# 3_DAC_Control_CH1_V2_0-2_4.net
KiCad netlist of a schematic drawn in Altium Designer
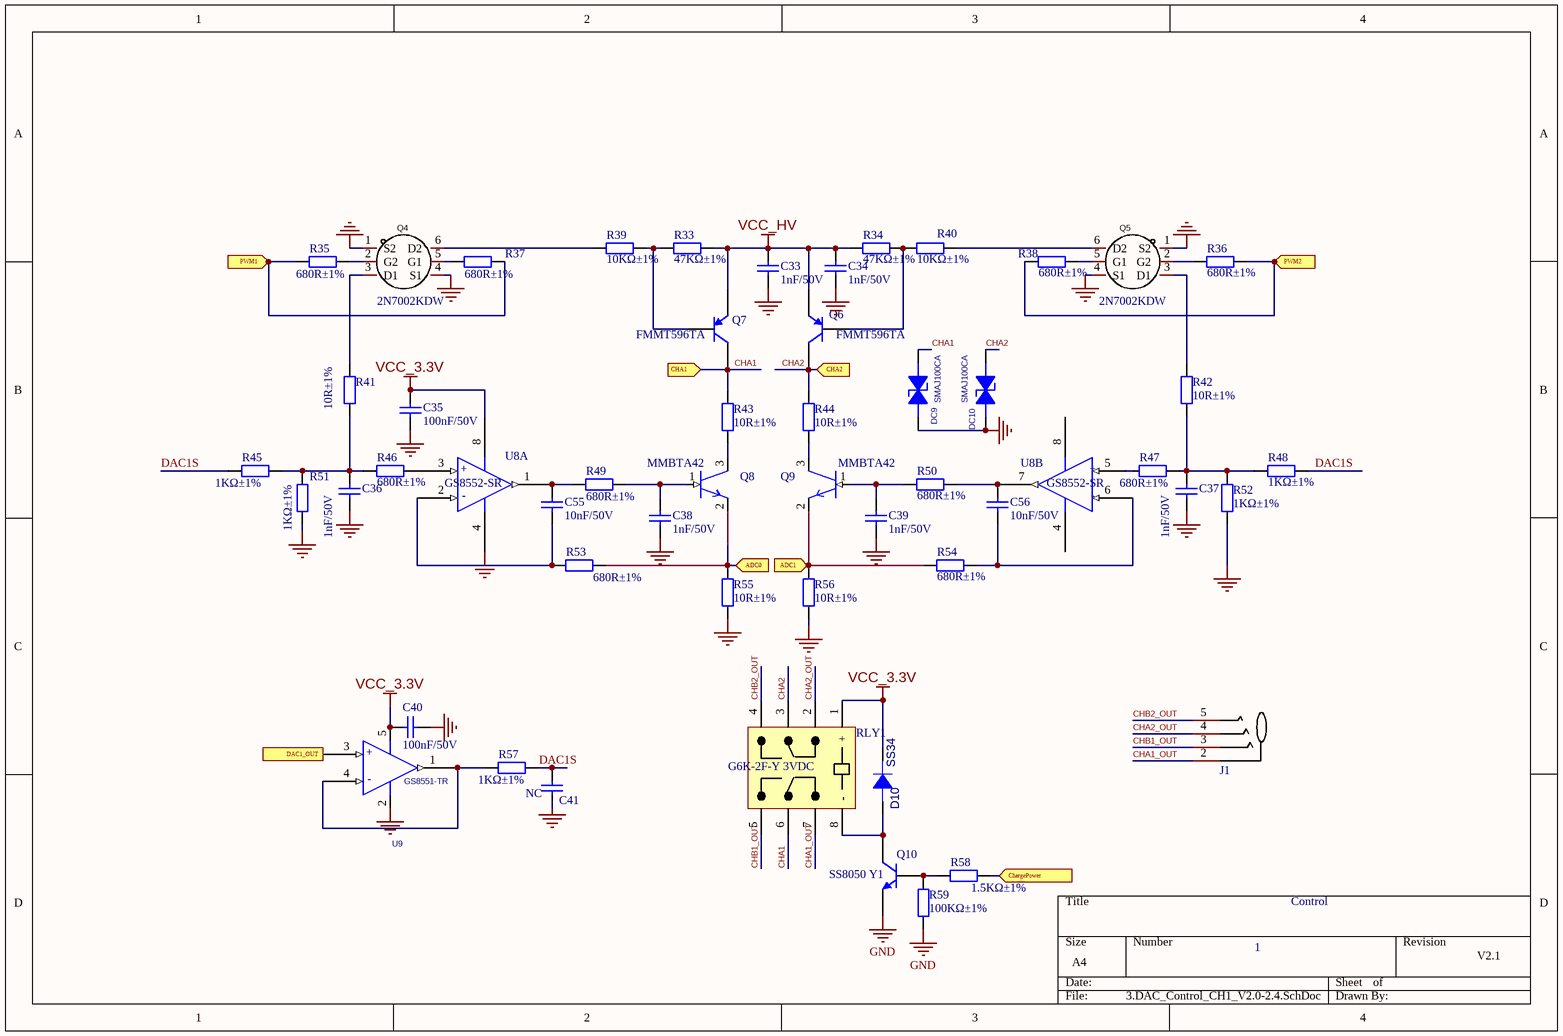
[diagram p0: 3.DAC_Control_CH1_V2.0-2.4.SchDoc]

(export (version "E")
  (design (tool "Eeschema 10.0.6"))
  (components
    (comp (ref "C33")
      (value "1nF/50V")
      (footprint "0603C")
      (description "贴片电容")
      (libsource (lib "Miscellaneous Devices LC") (part "0402 1nF (102) 10% 50V"))
    )
    (comp (ref "C34")
      (value "1nF/50V")
      (footprint "0603C")
      (description "贴片电容")
      (libsource (lib "Miscellaneous Devices LC") (part "0402 1nF (102) 10% 50V"))
    )
    (comp (ref "C35")
      (value "100nF/50V")
      (footprint "0603C")
      (description "贴片电容100nF 10% 50V")
      (libsource (lib "Miscellaneous Devices LC") (part "0402 100nF (104) 10% 16V"))
    )
    (comp (ref "C36")
      (value "1nF/50V")
      (footprint "0603C")
      (description "贴片电容")
      (libsource (lib "Miscellaneous Devices LC") (part "0402 10nF (103) 10% 50V"))
    )
    (comp (ref "C37")
      (value "1nF/50V")
      (footprint "0603C")
      (description "贴片电容")
      (libsource (lib "Miscellaneous Devices LC") (part "0402 10nF (103) 10% 50V"))
    )
    (comp (ref "C38")
      (value "1nF/50V")
      (footprint "0603C")
      (description "贴片电容")
      (libsource (lib "Miscellaneous Devices LC") (part "0402 10nF (103) 10% 50V"))
    )
    (comp (ref "C39")
      (value "1nF/50V")
      (footprint "0603C")
      (description "贴片电容")
      (libsource (lib "Miscellaneous Devices LC") (part "0402 10nF (103) 10% 50V"))
    )
    (comp (ref "C40")
      (value "100nF/50V")
      (footprint "0603C")
      (description "贴片电容100nF 10% 50V")
      (libsource (lib "Miscellaneous Devices LC") (part "0402 100nF (104) 10% 16V"))
    )
    (comp (ref "C41")
      (value "NC")
      (footprint "0603C")
      (description "贴片电容10uF/10V")
      (libsource (lib "Miscellaneous Devices LC") (part "0603 10uF (106) 10% 10V"))
    )
    (comp (ref "C55")
      (value "10nF/50V")
      (footprint "0603C")
      (description "贴片电容")
      (libsource (lib "Miscellaneous Devices LC") (part "0402 10nF (103) 10% 50V"))
    )
    (comp (ref "C56")
      (value "10nF/50V")
      (footprint "0603C")
      (description "贴片电容")
      (libsource (lib "Miscellaneous Devices LC") (part "0402 10nF (103) 10% 50V"))
    )
    (comp (ref "D10")
      (value "SS34")
      (footprint "SMA")
      (description "Schottky Barrier， DO214AA")
      (fields (field (name "MANUFACTURER") "星海") (field (name "CREATED_BY") "JJJ"))
      (libsource (lib "*") (part "DIODE_2"))
    )
    (comp (ref "DC9")
      (value "SMAJ100CA")
      (footprint "SMA")
      (description "SMAJ100CA  SMA(DO-214AC)")
      (libsource (lib "*") (part "ESD5451X_Dup1"))
    )
    (comp (ref "DC10")
      (value "SMAJ100CA")
      (footprint "SMA")
      (description "SMAJ100CA  SMA(DO-214AC)")
      (libsource (lib "*") (part "ESD5451X_Dup1"))
    )
    (comp (ref "J1")
      (value "PJ-320D 贴片4脚")
      (footprint "AUDIO-TH_L14.1-W6.1_PJ-320D")
      (libsource (lib "altium-import") (part "root_2_PJ-320D 贴片4脚_"))
    )
    (comp (ref "Q4")
      (value "2N7002KDW")
      (footprint "SOT-363")
      (description "TECH PUBLIC(台舟) SOT-363")
      (fields (field (name "MANUFACTURER") "TECH PUBLIC(台舟)"))
      (libsource (lib "altium-import") (part "root_0_2N7002KDW_"))
    )
    (comp (ref "Q5")
      (value "2N7002KDW")
      (footprint "SOT-363")
      (description "TECH PUBLIC(台舟) SOT-363")
      (fields (field (name "MANUFACTURER") "TECH PUBLIC(台舟)"))
      (libsource (lib "altium-import") (part "root_0_mirrored_2N7002KDW_"))
    )
    (comp (ref "Q6")
      (value "FMMT596TA")
      (footprint "SOT-23(SOT-23-3)")
      (description "三极管")
      (libsource (lib "Miscellaneous Devices LC") (part "SOT-23 SS8550 Y2"))
    )
    (comp (ref "Q7")
      (value "FMMT596TA")
      (footprint "SOT-23(SOT-23-3)")
      (description "三极管")
      (libsource (lib "Miscellaneous Devices LC") (part "SOT-23 SS8550 Y2"))
    )
    (comp (ref "Q8")
      (value "MMBTA42")
      (footprint "SOT-23")
      (description "CJ(江苏长电/长晶)")
      (libsource (lib "*") (part "NPN"))
    )
    (comp (ref "Q9")
      (value "MMBTA42")
      (footprint "SOT-23")
      (description "CJ(江苏长电/长晶)")
      (libsource (lib "*") (part "NPN"))
    )
    (comp (ref "Q10")
      (value "SS8050 Y1")
      (footprint "SOT-23(SOT-23-3)")
      (description "三极管")
      (libsource (lib "Miscellaneous Devices LC") (part "SOT-23 SS8050 Y1"))
    )
    (comp (ref "R33")
      (value "47KΩ±1%")
      (footprint "0603R")
      (description "贴片电阻")
      (libsource (lib "Miscellaneous Devices LC") (part "0402 1KΩ (1001) 1%"))
    )
    (comp (ref "R34")
      (value "47KΩ±1%")
      (footprint "0603R")
      (description "贴片电阻")
      (libsource (lib "") (part "0402 1KΩ (1001) 1%_1"))
    )
    (comp (ref "R35")
      (value "680R±1%")
      (footprint "0603R")
      (description "贴片电阻")
      (libsource (lib "Miscellaneous Devices LC") (part "0402 680Ω (6800) 1%"))
    )
    (comp (ref "R36")
      (value "680R±1%")
      (footprint "0603R")
      (description "贴片电阻")
      (libsource (lib "") (part "0402 680Ω (6800) 1%_1"))
    )
    (comp (ref "R37")
      (value "680R±1%")
      (footprint "0603R")
      (description "贴片电阻")
      (libsource (lib "Miscellaneous Devices LC") (part "0402 680Ω (6800) 1%"))
    )
    (comp (ref "R38")
      (value "680R±1%")
      (footprint "0603R")
      (description "贴片电阻")
      (libsource (lib "") (part "0402 680Ω (6800) 1%_1"))
    )
    (comp (ref "R39")
      (value "10KΩ±1%")
      (footprint "0603R")
      (description "贴片电阻")
      (libsource (lib "Miscellaneous Devices LC") (part "0402 1KΩ (1001) 1%"))
    )
    (comp (ref "R40")
      (value "10KΩ±1%")
      (footprint "0603R")
      (description "贴片电阻")
      (libsource (lib "") (part "0402 1KΩ (1001) 1%_1"))
    )
    (comp (ref "R41")
      (value "10R±1%")
      (footprint "0603R")
      (description "贴片电阻")
      (libsource (lib "") (part "0603 100Ω (1000) 1%_1"))
    )
    (comp (ref "R42")
      (value "10R±1%")
      (footprint "0603R")
      (description "贴片电阻")
      (libsource (lib "Miscellaneous Devices LC") (part "0603 100Ω (1000) 1%"))
    )
    (comp (ref "R43")
      (value "10R±1%")
      (footprint "0805_R")
      (description "贴片电阻")
      (libsource (lib "") (part "0603 100Ω (1000) 1%_1"))
    )
    (comp (ref "R44")
      (value "10R±1%")
      (footprint "0805_R")
      (description "贴片电阻")
      (libsource (lib "Miscellaneous Devices LC") (part "0603 100Ω (1000) 1%"))
    )
    (comp (ref "R45")
      (value "1KΩ±1%")
      (footprint "0603R")
      (description "贴片电阻")
      (libsource (lib "") (part "0402 1KΩ (1001) 1%_3"))
    )
    (comp (ref "R46")
      (value "680R±1%")
      (footprint "0603R")
      (description "贴片电阻")
      (libsource (lib "Miscellaneous Devices LC") (part "0402 680Ω (6800) 1%"))
    )
    (comp (ref "R47")
      (value "680R±1%")
      (footprint "0603R")
      (description "贴片电阻")
      (libsource (lib "") (part "0402 680Ω (6800) 1%_1"))
    )
    (comp (ref "R48")
      (value "1KΩ±1%")
      (footprint "0603R")
      (description "贴片电阻")
      (libsource (lib "") (part "0402 1KΩ (1001) 1%_2"))
    )
    (comp (ref "R49")
      (value "680R±1%")
      (footprint "0603R")
      (description "贴片电阻")
      (libsource (lib "Miscellaneous Devices LC") (part "0402 680Ω (6800) 1%"))
    )
    (comp (ref "R50")
      (value "680R±1%")
      (footprint "0603R")
      (description "贴片电阻")
      (libsource (lib "") (part "0402 680Ω (6800) 1%_1"))
    )
    (comp (ref "R51")
      (value "1KΩ±1%")
      (footprint "0603R")
      (description "贴片电阻")
      (libsource (lib "") (part "0402 1KΩ (1001) 1%_1"))
    )
    (comp (ref "R52")
      (value "1KΩ±1%")
      (footprint "0603R")
      (description "贴片电阻")
      (libsource (lib "") (part "0402 1KΩ (1001) 1%_3"))
    )
    (comp (ref "R53")
      (value "680R±1%")
      (footprint "0603R")
      (description "贴片电阻")
      (libsource (lib "Miscellaneous Devices LC") (part "0402 680Ω (6800) 1%"))
    )
    (comp (ref "R54")
      (value "680R±1%")
      (footprint "0603R")
      (description "贴片电阻")
      (libsource (lib "") (part "0402 680Ω (6800) 1%_1"))
    )
    (comp (ref "R55")
      (value "10R±1%")
      (footprint "0805_R")
      (description "贴片电阻")
      (libsource (lib "") (part "0603 100Ω (1000) 1%_1"))
    )
    (comp (ref "R56")
      (value "10R±1%")
      (footprint "0805_R")
      (description "贴片电阻")
      (libsource (lib "Miscellaneous Devices LC") (part "0603 100Ω (1000) 1%"))
    )
    (comp (ref "R57")
      (value "1KΩ±1%")
      (footprint "0603R")
      (description "贴片电阻")
      (libsource (lib "Miscellaneous Devices LC") (part "0402 1KΩ (1001) 1%"))
    )
    (comp (ref "R58")
      (value "1.5KΩ±1%")
      (footprint "0402_R")
      (description "贴片电阻")
      (libsource (lib "") (part "0402 1.5KΩ (1501) 1%_1"))
    )
    (comp (ref "R59")
      (value "100KΩ±1%")
      (footprint "0402_R")
      (description "贴片电阻")
      (libsource (lib "Miscellaneous Devices LC") (part "0402 1.5KΩ (1501) 1%"))
    )
    (comp (ref "RLY1")
      (value "G6K-2F-Y 3VDC")
      (footprint "HFD4/12")
      (libsource (lib "MySchLib") (part "RELAY(HF)"))
    )
    (comp (ref "U8")
      (value "GS8552-SR")
      (footprint "SOP-8_150mil")
      (libsource (lib "DESIGN6(1)_Library") (part "GS8552-SR"))
    )
    (comp (ref "U9")
      (value "GS8551-TR")
      (footprint "SOT-23-5")
      (description "GS8551-TR  GS8551 SOT-23-5")
      (fields
        (field (name "MANUFACTURER_PART_NUMBER") "OPA335AIDBVR")
        (field (name "COPYRIGHT") "Copyright (C) 2022 Ultra Librarian. All rights reserved.")
      )
      (libsource (lib "FES_VNS_V1.0x2") (part "OPA335AIDBVR_1"))
    )
  )
  (nets
    (net (code "1") (name "/ADC0") (class "Default")
      (node (ref "Q8") (pin "2") (pinfunction "2_2") (pintype "passive"))
      (node (ref "R53") (pin "2") (pinfunction "2_2") (pintype "passive"))
      (node (ref "R55") (pin "2") (pinfunction "2_2") (pintype "passive"))
    )
    (net (code "2") (name "/ADC1") (class "Default")
      (node (ref "Q9") (pin "2") (pinfunction "2_2") (pintype "passive"))
      (node (ref "R54") (pin "2") (pinfunction "2_2") (pintype "passive"))
      (node (ref "R56") (pin "2") (pinfunction "2_2") (pintype "passive"))
    )
    (net (code "3") (name "/CHA1") (class "Default")
      (node (ref "DC9") (pin "1") (pinfunction "ANODE_1") (pintype "passive"))
      (node (ref "Q7") (pin "3") (pinfunction "C_3") (pintype "passive"))
      (node (ref "R43") (pin "2") (pinfunction "2_2") (pintype "passive"))
      (node (ref "RLY1") (pin "6") (pinfunction "6_6") (pintype "passive"))
    )
    (net (code "4") (name "/CHA1_OUT") (class "Default")
      (node (ref "J1") (pin "2") (pinfunction "2_2") (pintype "passive"))
      (node (ref "RLY1") (pin "7") (pinfunction "7_7") (pintype "passive"))
    )
    (net (code "5") (name "/CHA2") (class "Default")
      (node (ref "DC10") (pin "1") (pinfunction "ANODE_1") (pintype "passive"))
      (node (ref "Q6") (pin "3") (pinfunction "C_3") (pintype "passive"))
      (node (ref "R44") (pin "2") (pinfunction "2_2") (pintype "passive"))
      (node (ref "RLY1") (pin "3") (pinfunction "3_3") (pintype "passive"))
    )
    (net (code "6") (name "/CHA2_OUT") (class "Default")
      (node (ref "J1") (pin "4") (pinfunction "4_4") (pintype "passive"))
      (node (ref "RLY1") (pin "2") (pinfunction "2_2") (pintype "passive"))
    )
    (net (code "7") (name "/CHB1_OUT") (class "Default")
      (node (ref "J1") (pin "3") (pinfunction "3_3") (pintype "passive"))
      (node (ref "RLY1") (pin "5") (pinfunction "5_5") (pintype "passive"))
    )
    (net (code "8") (name "/CHB2_OUT") (class "Default")
      (node (ref "J1") (pin "5") (pinfunction "5_5") (pintype "passive"))
      (node (ref "RLY1") (pin "4") (pinfunction "4_4") (pintype "passive"))
    )
    (net (code "9") (name "/ChargePower") (class "Default")
      (node (ref "R58") (pin "1") (pinfunction "1_1") (pintype "passive"))
    )
    (net (code "10") (name "/DAC1S") (class "Default")
      (node (ref "C41") (pin "2") (pinfunction "2_2") (pintype "passive"))
      (node (ref "R45") (pin "1") (pinfunction "1_1") (pintype "passive"))
      (node (ref "R48") (pin "1") (pinfunction "1_1") (pintype "passive"))
      (node (ref "R57") (pin "1") (pinfunction "1_1") (pintype "passive"))
    )
    (net (code "11") (name "/DAC1_OUT") (class "Default")
      (node (ref "U9") (pin "3") (pinfunction "IN+_3") (pintype "input"))
    )
    (net (code "12") (name "/PWM1") (class "Default")
      (node (ref "R35") (pin "1") (pinfunction "1_1") (pintype "passive"))
      (node (ref "R37") (pin "2") (pinfunction "2_2") (pintype "passive"))
    )
    (net (code "13") (name "/PWM2") (class "Default")
      (node (ref "R36") (pin "1") (pinfunction "1_1") (pintype "passive"))
      (node (ref "R38") (pin "2") (pinfunction "2_2") (pintype "passive"))
    )
    (net (code "14") (name "GND") (class "Default")
      (node (ref "C33") (pin "1") (pinfunction "1_1") (pintype "passive"))
      (node (ref "C34") (pin "1") (pinfunction "1_1") (pintype "passive"))
      (node (ref "C35") (pin "1") (pinfunction "1_1") (pintype "passive"))
      (node (ref "C36") (pin "1") (pinfunction "1_1") (pintype "passive"))
      (node (ref "C37") (pin "1") (pinfunction "1_1") (pintype "passive"))
      (node (ref "C38") (pin "1") (pinfunction "1_1") (pintype "passive"))
      (node (ref "C39") (pin "1") (pinfunction "1_1") (pintype "passive"))
      (node (ref "C40") (pin "1") (pinfunction "1_1") (pintype "passive"))
      (node (ref "C41") (pin "1") (pinfunction "1_1") (pintype "passive"))
      (node (ref "DC10") (pin "2") (pinfunction "CATHODE_2") (pintype "passive"))
      (node (ref "DC9") (pin "2") (pinfunction "CATHODE_2") (pintype "passive"))
      (node (ref "Q10") (pin "2") (pinfunction "E_2") (pintype "passive"))
      (node (ref "Q4") (pin "1") (pinfunction "S2_1") (pintype "passive"))
      (node (ref "Q4") (pin "4") (pinfunction "S1_4") (pintype "passive"))
      (node (ref "Q5") (pin "1") (pinfunction "S2_1") (pintype "passive"))
      (node (ref "Q5") (pin "4") (pinfunction "S1_4") (pintype "passive"))
      (node (ref "R51") (pin "1") (pinfunction "1_1") (pintype "passive"))
      (node (ref "R52") (pin "1") (pinfunction "1_1") (pintype "passive"))
      (node (ref "R55") (pin "1") (pinfunction "1_1") (pintype "passive"))
      (node (ref "R56") (pin "1") (pinfunction "1_1") (pintype "passive"))
      (node (ref "R59") (pin "1") (pinfunction "1_1") (pintype "passive"))
      (node (ref "U8") (pin "4") (pinfunction "GND_4") (pintype "power_in"))
      (node (ref "U9") (pin "2") (pinfunction "V-_2") (pintype "power_in"))
    )
    (net (code "15") (name "Net-(C36-Pad2)") (class "Default")
      (node (ref "C36") (pin "2") (pinfunction "2_2") (pintype "passive"))
      (node (ref "R41") (pin "1") (pinfunction "1_1") (pintype "passive"))
      (node (ref "R45") (pin "2") (pinfunction "2_2") (pintype "passive"))
      (node (ref "R46") (pin "1") (pinfunction "1_1") (pintype "passive"))
      (node (ref "R51") (pin "2") (pinfunction "2_2") (pintype "passive"))
    )
    (net (code "16") (name "Net-(C37-Pad2)") (class "Default")
      (node (ref "C37") (pin "2") (pinfunction "2_2") (pintype "passive"))
      (node (ref "R42") (pin "1") (pinfunction "1_1") (pintype "passive"))
      (node (ref "R47") (pin "1") (pinfunction "1_1") (pintype "passive"))
      (node (ref "R48") (pin "2") (pinfunction "2_2") (pintype "passive"))
      (node (ref "R52") (pin "2") (pinfunction "2_2") (pintype "passive"))
    )
    (net (code "17") (name "Net-(C38-Pad2)") (class "Default")
      (node (ref "C38") (pin "2") (pinfunction "2_2") (pintype "passive"))
      (node (ref "Q8") (pin "1") (pinfunction "1_1") (pintype "input"))
      (node (ref "R49") (pin "2") (pinfunction "2_2") (pintype "passive"))
    )
    (net (code "18") (name "Net-(C39-Pad2)") (class "Default")
      (node (ref "C39") (pin "2") (pinfunction "2_2") (pintype "passive"))
      (node (ref "Q9") (pin "1") (pinfunction "1_1") (pintype "input"))
      (node (ref "R50") (pin "2") (pinfunction "2_2") (pintype "passive"))
    )
    (net (code "19") (name "Net-(D10-A)") (class "Default")
      (node (ref "D10") (pin "1") (pinfunction "A_1") (pintype "passive"))
      (node (ref "Q10") (pin "3") (pinfunction "C_3") (pintype "passive"))
      (node (ref "RLY1") (pin "8") (pinfunction "-_8") (pintype "passive"))
    )
    (net (code "20") (name "Net-(Q4-D1)") (class "Default")
      (node (ref "Q4") (pin "3") (pinfunction "D1_3") (pintype "passive"))
      (node (ref "R41") (pin "2") (pinfunction "2_2") (pintype "passive"))
    )
    (net (code "21") (name "Net-(Q4-D2)") (class "Default")
      (node (ref "Q4") (pin "6") (pinfunction "D2_6") (pintype "passive"))
      (node (ref "R39") (pin "2") (pinfunction "2_2") (pintype "passive"))
    )
    (net (code "22") (name "Net-(Q4-G1)") (class "Default")
      (node (ref "Q4") (pin "5") (pinfunction "G1_5") (pintype "passive"))
      (node (ref "R37") (pin "1") (pinfunction "1_1") (pintype "passive"))
    )
    (net (code "23") (name "Net-(Q4-G2)") (class "Default")
      (node (ref "Q4") (pin "2") (pinfunction "G2_2") (pintype "passive"))
      (node (ref "R35") (pin "2") (pinfunction "2_2") (pintype "passive"))
    )
    (net (code "24") (name "Net-(Q5-D1)") (class "Default")
      (node (ref "Q5") (pin "3") (pinfunction "D1_3") (pintype "passive"))
      (node (ref "R42") (pin "2") (pinfunction "2_2") (pintype "passive"))
    )
    (net (code "25") (name "Net-(Q5-D2)") (class "Default")
      (node (ref "Q5") (pin "6") (pinfunction "D2_6") (pintype "passive"))
      (node (ref "R40") (pin "2") (pinfunction "2_2") (pintype "passive"))
    )
    (net (code "26") (name "Net-(Q5-G1)") (class "Default")
      (node (ref "Q5") (pin "5") (pinfunction "G1_5") (pintype "passive"))
      (node (ref "R38") (pin "1") (pinfunction "1_1") (pintype "passive"))
    )
    (net (code "27") (name "Net-(Q5-G2)") (class "Default")
      (node (ref "Q5") (pin "2") (pinfunction "G2_2") (pintype "passive"))
      (node (ref "R36") (pin "2") (pinfunction "2_2") (pintype "passive"))
    )
    (net (code "28") (name "Net-(Q6-B)") (class "Default")
      (node (ref "Q6") (pin "1") (pinfunction "B_1") (pintype "passive"))
      (node (ref "R34") (pin "2") (pinfunction "2_2") (pintype "passive"))
      (node (ref "R40") (pin "1") (pinfunction "1_1") (pintype "passive"))
    )
    (net (code "29") (name "Net-(Q7-B)") (class "Default")
      (node (ref "Q7") (pin "1") (pinfunction "B_1") (pintype "passive"))
      (node (ref "R33") (pin "2") (pinfunction "2_2") (pintype "passive"))
      (node (ref "R39") (pin "1") (pinfunction "1_1") (pintype "passive"))
    )
    (net (code "30") (name "Net-(Q8-Pad3)") (class "Default")
      (node (ref "Q8") (pin "3") (pinfunction "3_3") (pintype "passive"))
      (node (ref "R43") (pin "1") (pinfunction "1_1") (pintype "passive"))
    )
    (net (code "31") (name "Net-(Q9-Pad3)") (class "Default")
      (node (ref "Q9") (pin "3") (pinfunction "3_3") (pintype "passive"))
      (node (ref "R44") (pin "1") (pinfunction "1_1") (pintype "passive"))
    )
    (net (code "32") (name "Net-(Q10-B)") (class "Default")
      (node (ref "Q10") (pin "1") (pinfunction "B_1") (pintype "passive"))
      (node (ref "R58") (pin "2") (pinfunction "2_2") (pintype "passive"))
      (node (ref "R59") (pin "2") (pinfunction "2_2") (pintype "passive"))
    )
    (net (code "33") (name "Net-(U8A-+IN)") (class "Default")
      (node (ref "R46") (pin "2") (pinfunction "2_2") (pintype "passive"))
      (node (ref "U8") (pin "3") (pinfunction "+IN_3") (pintype "input"))
    )
    (net (code "34") (name "Net-(U8A--IN)") (class "Default")
      (node (ref "C55") (pin "1") (pinfunction "1_1") (pintype "passive"))
      (node (ref "R53") (pin "1") (pinfunction "1_1") (pintype "passive"))
      (node (ref "U8") (pin "2") (pinfunction "-IN_2") (pintype "input"))
    )
    (net (code "35") (name "Net-(U8A-OUT)") (class "Default")
      (node (ref "C55") (pin "2") (pinfunction "2_2") (pintype "passive"))
      (node (ref "R49") (pin "1") (pinfunction "1_1") (pintype "passive"))
      (node (ref "U8") (pin "1") (pinfunction "OUT_1") (pintype "output"))
    )
    (net (code "36") (name "Net-(U8B-+IN)") (class "Default")
      (node (ref "R47") (pin "2") (pinfunction "2_2") (pintype "passive"))
      (node (ref "U8") (pin "5") (pinfunction "+IN_5") (pintype "input"))
    )
    (net (code "37") (name "Net-(U8B--IN)") (class "Default")
      (node (ref "C56") (pin "1") (pinfunction "1_1") (pintype "passive"))
      (node (ref "R54") (pin "1") (pinfunction "1_1") (pintype "passive"))
      (node (ref "U8") (pin "6") (pinfunction "-IN_6") (pintype "input"))
    )
    (net (code "38") (name "Net-(U8B-OUT)") (class "Default")
      (node (ref "C56") (pin "2") (pinfunction "2_2") (pintype "passive"))
      (node (ref "R50") (pin "1") (pinfunction "1_1") (pintype "passive"))
      (node (ref "U8") (pin "7") (pinfunction "OUT_7") (pintype "output"))
    )
    (net (code "39") (name "Net-(U9-IN-)") (class "Default")
      (node (ref "R57") (pin "2") (pinfunction "2_2") (pintype "passive"))
      (node (ref "U9") (pin "1") (pinfunction "OUT_1") (pintype "output"))
      (node (ref "U9") (pin "4") (pinfunction "IN-_4") (pintype "input"))
    )
    (net (code "40") (name "VCC_3.3V") (class "Default")
      (node (ref "C35") (pin "2") (pinfunction "2_2") (pintype "passive"))
      (node (ref "C40") (pin "2") (pinfunction "2_2") (pintype "passive"))
      (node (ref "D10") (pin "2") (pinfunction "K_2") (pintype "passive"))
      (node (ref "RLY1") (pin "1") (pinfunction "+_1") (pintype "passive"))
      (node (ref "U8") (pin "8") (pinfunction "VCC_8") (pintype "power_in"))
      (node (ref "U9") (pin "5") (pinfunction "V+_5") (pintype "power_in"))
    )
    (net (code "41") (name "VCC_HV") (class "Default")
      (node (ref "C33") (pin "2") (pinfunction "2_2") (pintype "passive"))
      (node (ref "C34") (pin "2") (pinfunction "2_2") (pintype "passive"))
      (node (ref "Q6") (pin "2") (pinfunction "E_2") (pintype "passive"))
      (node (ref "Q7") (pin "2") (pinfunction "E_2") (pintype "passive"))
      (node (ref "R33") (pin "1") (pinfunction "1_1") (pintype "passive"))
      (node (ref "R34") (pin "1") (pinfunction "1_1") (pintype "passive"))
    )
    (net (code "42") (name "unconnected-(U8B-GND-Pad4)") (class "Default")
      (node (ref "U8") (pin "4") (pinfunction "GND_4") (pintype "power_in"))
    )
    (net (code "43") (name "unconnected-(U8B-VCC-Pad8)") (class "Default")
      (node (ref "U8") (pin "8") (pinfunction "VCC_8") (pintype "power_in"))
    )
  )
)
